# Ctrl-PWM.net
KiCad netlist of a schematic drawn in Altium Designer
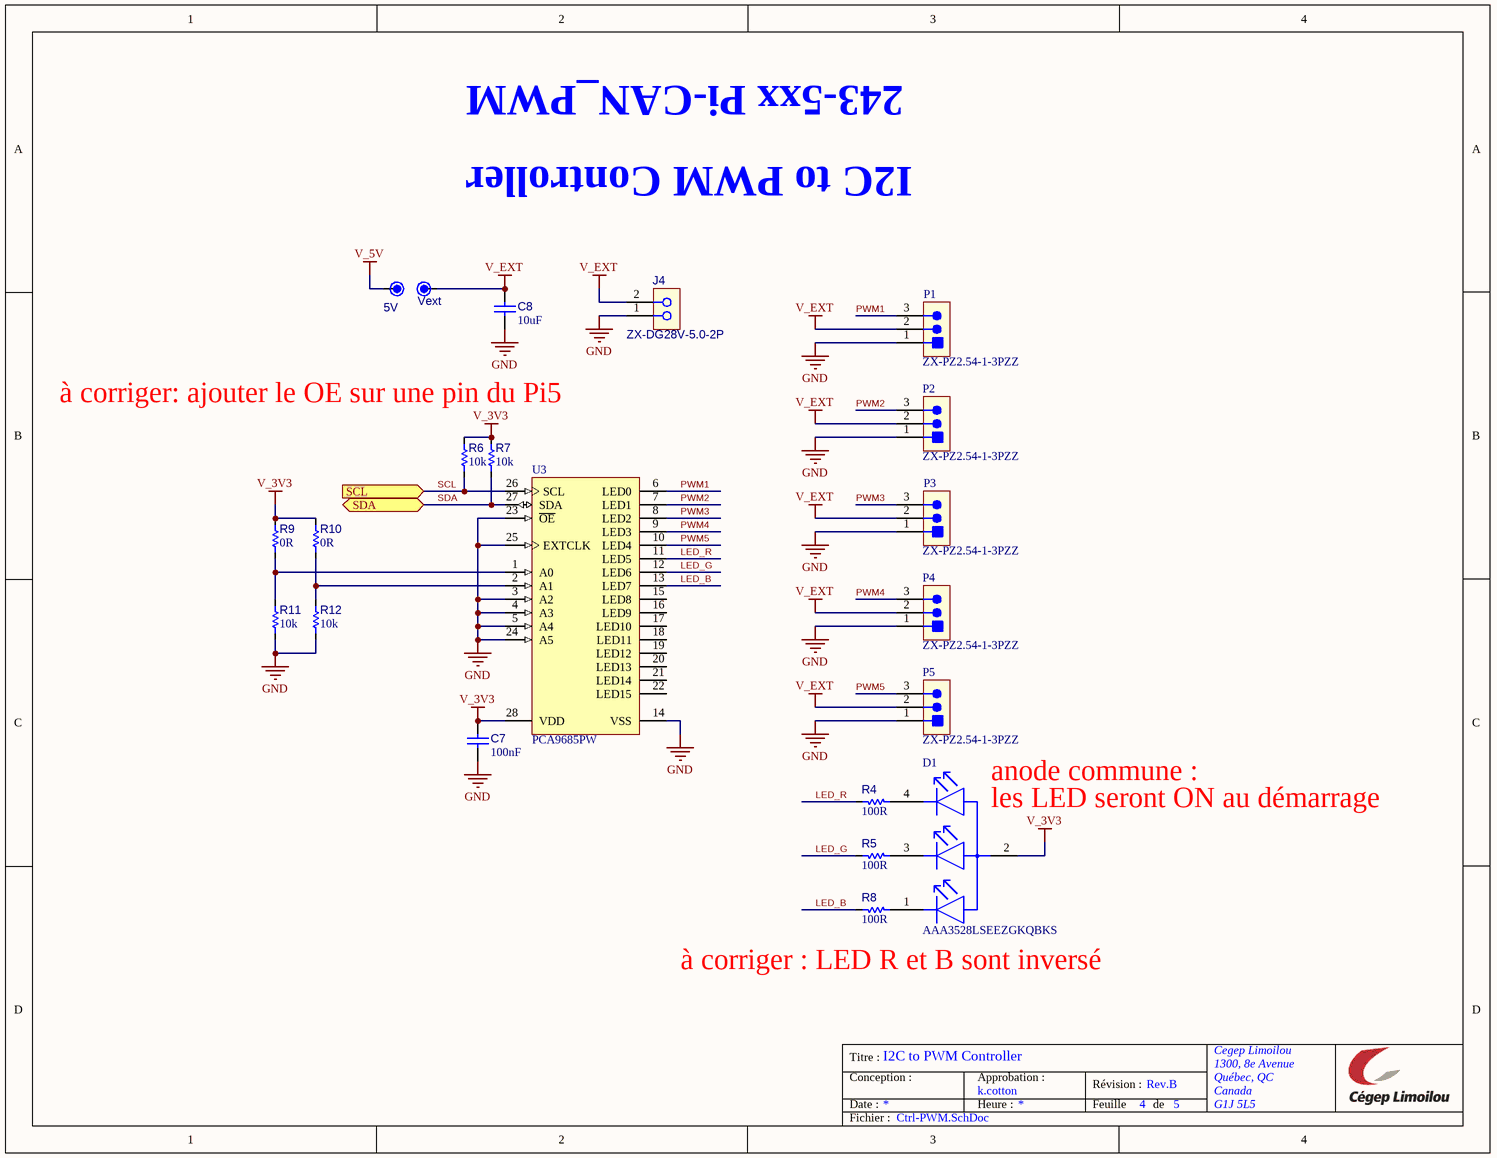
[diagram p0: Ctrl-PWM.SchDoc]

(export (version "E")
  (design (tool "Eeschema 10.0.6"))
  (components
    (comp (ref "5V")
      (value "DNP")
      (footprint "TP_TH061")
      (description "Pad TH 0.61mm diameter (AWG28)")
      (libsource (lib "243-436_MP_Console") (part "TP_TH0.61mm(AWG28)"))
    )
    (comp (ref "C7")
      (value "100nF")
      (footprint "C_1005[0402]")
      (description "Capacitor type 1")
      (fields (field (name "TOLERANCE") "10%") (field (name "Comment") "CAP CER 100nF 50V 0402"))
      (libsource (lib "TEP-AltiumLib-Passives-RLC") (part "capacitor"))
    )
    (comp (ref "C8")
      (value "10uF")
      (footprint "C_2012[0805]")
      (description "Capacitor type 1")
      (fields (field (name "TOLERANCE") "10%") (field (name "Comment") "CAP CER 10uF 10V X7R 0805"))
      (libsource (lib "TEP-AltiumLib-Passives-RLC") (part "capacitor"))
    )
    (comp (ref "D1")
      (value "AAA3528LSEEZGKQBKS")
      (footprint "FP-AAA3528LSEEZGKQBKS-MFG")
      (description "LED RGB CLEAR 4SMD")
      (libsource (lib "Altium Content Vault") (part "90ad27b0ccda589ca0f9bdbe0fe36f4"))
    )
    (comp (ref "J4")
      (value "ZX-DG28V-5.0-2P")
      (footprint "CONN_TERM_BLOCK_2POS_5mm_Model1")
      (description "CONN TERM BLOCK 2POS 5mm pitch")
      (libsource (lib "TEP-AltiumLib-Connectors") (part "CONN-5MM-2POS-TERM-BLOCK"))
    )
    (comp (ref "P1")
      (value "ZX-PZ2.54-1-3PZZ")
      (footprint "CONN_HDR_3POS_100MILS_TH")
      (description "CONN HEADER 3pins single row, 100 mils TH")
      (libsource (lib "TEP-AltiumLib-Connectors") (part "CONN-100MIL-HDR-01X03"))
    )
    (comp (ref "P2")
      (value "ZX-PZ2.54-1-3PZZ")
      (footprint "CONN_HDR_3POS_100MILS_TH")
      (description "CONN HEADER 3pins single row, 100 mils TH")
      (libsource (lib "TEP-AltiumLib-Connectors") (part "CONN-100MIL-HDR-01X03"))
    )
    (comp (ref "P3")
      (value "ZX-PZ2.54-1-3PZZ")
      (footprint "CONN_HDR_3POS_100MILS_TH")
      (description "CONN HEADER 3pins single row, 100 mils TH")
      (libsource (lib "TEP-AltiumLib-Connectors") (part "CONN-100MIL-HDR-01X03"))
    )
    (comp (ref "P4")
      (value "ZX-PZ2.54-1-3PZZ")
      (footprint "CONN_HDR_3POS_100MILS_TH")
      (description "CONN HEADER 3pins single row, 100 mils TH")
      (libsource (lib "TEP-AltiumLib-Connectors") (part "CONN-100MIL-HDR-01X03"))
    )
    (comp (ref "P5")
      (value "ZX-PZ2.54-1-3PZZ")
      (footprint "CONN_HDR_3POS_100MILS_TH")
      (description "CONN HEADER 3pins single row, 100 mils TH")
      (libsource (lib "TEP-AltiumLib-Connectors") (part "CONN-100MIL-HDR-01X03"))
    )
    (comp (ref "R4")
      (value "100R")
      (footprint "R_1608[0603]")
      (description "Resistor type 1")
      (fields (field (name "TOLERANCE") "1%") (field (name "Comment") "Res 100R 1% 0603"))
      (libsource (lib "TEP-AltiumLib-Passives-RLC") (part "resistor"))
    )
    (comp (ref "R5")
      (value "100R")
      (footprint "R_1608[0603]")
      (description "Resistor type 1")
      (fields (field (name "TOLERANCE") "1%") (field (name "Comment") "Res 100R 1% 0603"))
      (libsource (lib "TEP-AltiumLib-Passives-RLC") (part "resistor"))
    )
    (comp (ref "R6")
      (value "10k")
      (footprint "R_1005[0402]")
      (description "Resistor type 1")
      (fields (field (name "TOLERANCE") "1%") (field (name "Comment") "Res 10k 1% 0402"))
      (libsource (lib "TEP-AltiumLib-Passives-RLC") (part "resistor"))
    )
    (comp (ref "R7")
      (value "10k")
      (footprint "R_1005[0402]")
      (description "Resistor type 1")
      (fields (field (name "TOLERANCE") "1%") (field (name "Comment") "Res 10k 1% 0402"))
      (libsource (lib "TEP-AltiumLib-Passives-RLC") (part "resistor"))
    )
    (comp (ref "R8")
      (value "100R")
      (footprint "R_1608[0603]")
      (description "Resistor type 1")
      (fields (field (name "TOLERANCE") "1%") (field (name "Comment") "Res 100R 1% 0603"))
      (libsource (lib "TEP-AltiumLib-Passives-RLC") (part "resistor"))
    )
    (comp (ref "R9")
      (value "0R")
      (footprint "R_1005[0402]")
      (description "Resistor type 1")
      (fields (field (name "Comment") "DNP"))
      (libsource (lib "TEP-AltiumLib-Passives-RLC") (part "resistor"))
    )
    (comp (ref "R10")
      (value "0R")
      (footprint "R_1005[0402]")
      (description "Resistor type 1")
      (fields (field (name "Comment") "DNP"))
      (libsource (lib "TEP-AltiumLib-Passives-RLC") (part "resistor"))
    )
    (comp (ref "R11")
      (value "10k")
      (footprint "R_1005[0402]")
      (description "Resistor type 1")
      (fields (field (name "TOLERANCE") "1%") (field (name "Comment") "Res 10k 1% 0402"))
      (libsource (lib "TEP-AltiumLib-Passives-RLC") (part "resistor"))
    )
    (comp (ref "R12")
      (value "10k")
      (footprint "R_1005[0402]")
      (description "Resistor type 1")
      (fields (field (name "TOLERANCE") "1%") (field (name "Comment") "Res 10k 1% 0402"))
      (libsource (lib "TEP-AltiumLib-Passives-RLC") (part "resistor"))
    )
    (comp (ref "U3")
      (value "PCA9685PW")
      (footprint "TSSOP28_SOT361-1_V")
      (description "16-Channel, 12-Bit PWM I2C-Bus LED Controller, 28-Pin TSSOP (SOT361-1)")
      (libsource (lib "247-616_Pi-CAN") (part "U_PCA9685PW"))
    )
    (comp (ref "Vext")
      (value "DNP")
      (footprint "TP_TH061")
      (description "Pad TH 0.61mm diameter (AWG28)")
      (libsource (lib "243-436_MP_Console") (part "TP_TH0.61mm(AWG28)"))
    )
  )
  (nets
    (net (code "1") (name "/LED_B") (class "Default")
      (node (ref "R8") (pin "2") (pinfunction "2_2") (pintype "passive"))
      (node (ref "U3") (pin "13") (pinfunction "LED7_13") (pintype "tri_state"))
    )
    (net (code "2") (name "/LED_G") (class "Default")
      (node (ref "R5") (pin "2") (pinfunction "2_2") (pintype "passive"))
      (node (ref "U3") (pin "12") (pinfunction "LED6_12") (pintype "tri_state"))
    )
    (net (code "3") (name "/LED_R") (class "Default")
      (node (ref "R4") (pin "2") (pinfunction "2_2") (pintype "passive"))
      (node (ref "U3") (pin "11") (pinfunction "LED5_11") (pintype "tri_state"))
    )
    (net (code "4") (name "/PWM1") (class "Default")
      (node (ref "P1") (pin "3") (pinfunction "3_3") (pintype "passive"))
      (node (ref "U3") (pin "6") (pinfunction "LED0_6") (pintype "tri_state"))
    )
    (net (code "5") (name "/PWM2") (class "Default")
      (node (ref "P2") (pin "3") (pinfunction "3_3") (pintype "passive"))
      (node (ref "U3") (pin "7") (pinfunction "LED1_7") (pintype "tri_state"))
    )
    (net (code "6") (name "/PWM3") (class "Default")
      (node (ref "P3") (pin "3") (pinfunction "3_3") (pintype "passive"))
      (node (ref "U3") (pin "8") (pinfunction "LED2_8") (pintype "tri_state"))
    )
    (net (code "7") (name "/PWM4") (class "Default")
      (node (ref "P4") (pin "3") (pinfunction "3_3") (pintype "passive"))
      (node (ref "U3") (pin "9") (pinfunction "LED3_9") (pintype "tri_state"))
    )
    (net (code "8") (name "/PWM5") (class "Default")
      (node (ref "P5") (pin "3") (pinfunction "3_3") (pintype "passive"))
      (node (ref "U3") (pin "10") (pinfunction "LED4_10") (pintype "tri_state"))
    )
    (net (code "9") (name "/SCL") (class "Default")
      (node (ref "R6") (pin "1") (pinfunction "1_1") (pintype "passive"))
      (node (ref "U3") (pin "26") (pinfunction "SCL_26") (pintype "input"))
    )
    (net (code "10") (name "/SDA") (class "Default")
      (node (ref "R7") (pin "1") (pinfunction "1_1") (pintype "passive"))
      (node (ref "U3") (pin "27") (pinfunction "SDA_27") (pintype "bidirectional"))
    )
    (net (code "11") (name "GND") (class "Default")
      (node (ref "C7") (pin "1") (pinfunction "1_1") (pintype "passive"))
      (node (ref "C8") (pin "1") (pinfunction "1_1") (pintype "passive"))
      (node (ref "J4") (pin "1") (pinfunction "1_1") (pintype "passive"))
      (node (ref "P1") (pin "1") (pinfunction "1_1") (pintype "passive"))
      (node (ref "P2") (pin "1") (pinfunction "1_1") (pintype "passive"))
      (node (ref "P3") (pin "1") (pinfunction "1_1") (pintype "passive"))
      (node (ref "P4") (pin "1") (pinfunction "1_1") (pintype "passive"))
      (node (ref "P5") (pin "1") (pinfunction "1_1") (pintype "passive"))
      (node (ref "R11") (pin "1") (pinfunction "1_1") (pintype "passive"))
      (node (ref "R12") (pin "1") (pinfunction "1_1") (pintype "passive"))
      (node (ref "U3") (pin "14") (pinfunction "VSS_14") (pintype "power_in"))
      (node (ref "U3") (pin "23") (pinfunction "~{OE}_23") (pintype "input"))
      (node (ref "U3") (pin "24") (pinfunction "A5_24") (pintype "input"))
      (node (ref "U3") (pin "25") (pinfunction "EXTCLK_25") (pintype "input"))
      (node (ref "U3") (pin "3") (pinfunction "A2_3") (pintype "input"))
      (node (ref "U3") (pin "4") (pinfunction "A3_4") (pintype "input"))
      (node (ref "U3") (pin "5") (pinfunction "A4_5") (pintype "input"))
    )
    (net (code "12") (name "Net-(D1-BLUE_C)") (class "Default")
      (node (ref "D1") (pin "4") (pinfunction "BLUE_C_4") (pintype "passive"))
      (node (ref "R4") (pin "1") (pinfunction "1_1") (pintype "passive"))
    )
    (net (code "13") (name "Net-(D1-GREEN_C)") (class "Default")
      (node (ref "D1") (pin "3") (pinfunction "GREEN_C_3") (pintype "passive"))
      (node (ref "R5") (pin "1") (pinfunction "1_1") (pintype "passive"))
    )
    (net (code "14") (name "Net-(D1-RED_C)") (class "Default")
      (node (ref "D1") (pin "1") (pinfunction "RED_C_1") (pintype "passive"))
      (node (ref "R8") (pin "1") (pinfunction "1_1") (pintype "passive"))
    )
    (net (code "15") (name "Net-(U3-A0)") (class "Default")
      (node (ref "R11") (pin "2") (pinfunction "2_2") (pintype "passive"))
      (node (ref "R9") (pin "1") (pinfunction "1_1") (pintype "passive"))
      (node (ref "U3") (pin "1") (pinfunction "A0_1") (pintype "input"))
    )
    (net (code "16") (name "Net-(U3-A1)") (class "Default")
      (node (ref "R10") (pin "1") (pinfunction "1_1") (pintype "passive"))
      (node (ref "R12") (pin "2") (pinfunction "2_2") (pintype "passive"))
      (node (ref "U3") (pin "2") (pinfunction "A1_2") (pintype "input"))
    )
    (net (code "17") (name "V_3V3") (class "Default")
      (node (ref "C7") (pin "2") (pinfunction "2_2") (pintype "passive"))
      (node (ref "D1") (pin "2") (pinfunction "COMMON_ANODE_2") (pintype "passive"))
      (node (ref "R10") (pin "2") (pinfunction "2_2") (pintype "passive"))
      (node (ref "R6") (pin "2") (pinfunction "2_2") (pintype "passive"))
      (node (ref "R7") (pin "2") (pinfunction "2_2") (pintype "passive"))
      (node (ref "R9") (pin "2") (pinfunction "2_2") (pintype "passive"))
      (node (ref "U3") (pin "28") (pinfunction "VDD_28") (pintype "power_in"))
    )
    (net (code "18") (name "V_5V") (class "Default")
      (node (ref "5V") (pin "1") (pinfunction "1_1") (pintype "passive"))
    )
    (net (code "19") (name "V_EXT") (class "Default")
      (node (ref "C8") (pin "2") (pinfunction "2_2") (pintype "passive"))
      (node (ref "J4") (pin "2") (pinfunction "2_2") (pintype "passive"))
      (node (ref "P1") (pin "2") (pinfunction "2_2") (pintype "passive"))
      (node (ref "P2") (pin "2") (pinfunction "2_2") (pintype "passive"))
      (node (ref "P3") (pin "2") (pinfunction "2_2") (pintype "passive"))
      (node (ref "P4") (pin "2") (pinfunction "2_2") (pintype "passive"))
      (node (ref "P5") (pin "2") (pinfunction "2_2") (pintype "passive"))
      (node (ref "Vext") (pin "1") (pinfunction "1_1") (pintype "passive"))
    )
    (net (code "20") (name "unconnected-(U3-LED8-Pad15)") (class "Default")
      (node (ref "U3") (pin "15") (pinfunction "LED8_15") (pintype "tri_state"))
    )
    (net (code "21") (name "unconnected-(U3-LED9-Pad16)") (class "Default")
      (node (ref "U3") (pin "16") (pinfunction "LED9_16") (pintype "tri_state"))
    )
    (net (code "22") (name "unconnected-(U3-LED10-Pad17)") (class "Default")
      (node (ref "U3") (pin "17") (pinfunction "LED10_17") (pintype "tri_state"))
    )
    (net (code "23") (name "unconnected-(U3-LED11-Pad18)") (class "Default")
      (node (ref "U3") (pin "18") (pinfunction "LED11_18") (pintype "tri_state"))
    )
    (net (code "24") (name "unconnected-(U3-LED12-Pad19)") (class "Default")
      (node (ref "U3") (pin "19") (pinfunction "LED12_19") (pintype "tri_state"))
    )
    (net (code "25") (name "unconnected-(U3-LED13-Pad20)") (class "Default")
      (node (ref "U3") (pin "20") (pinfunction "LED13_20") (pintype "tri_state"))
    )
    (net (code "26") (name "unconnected-(U3-LED14-Pad21)") (class "Default")
      (node (ref "U3") (pin "21") (pinfunction "LED14_21") (pintype "tri_state"))
    )
    (net (code "27") (name "unconnected-(U3-LED15-Pad22)") (class "Default")
      (node (ref "U3") (pin "22") (pinfunction "LED15_22") (pintype "tri_state"))
    )
  )
)
